# Inverter.net
KiCad netlist of a schematic drawn in EAGLE
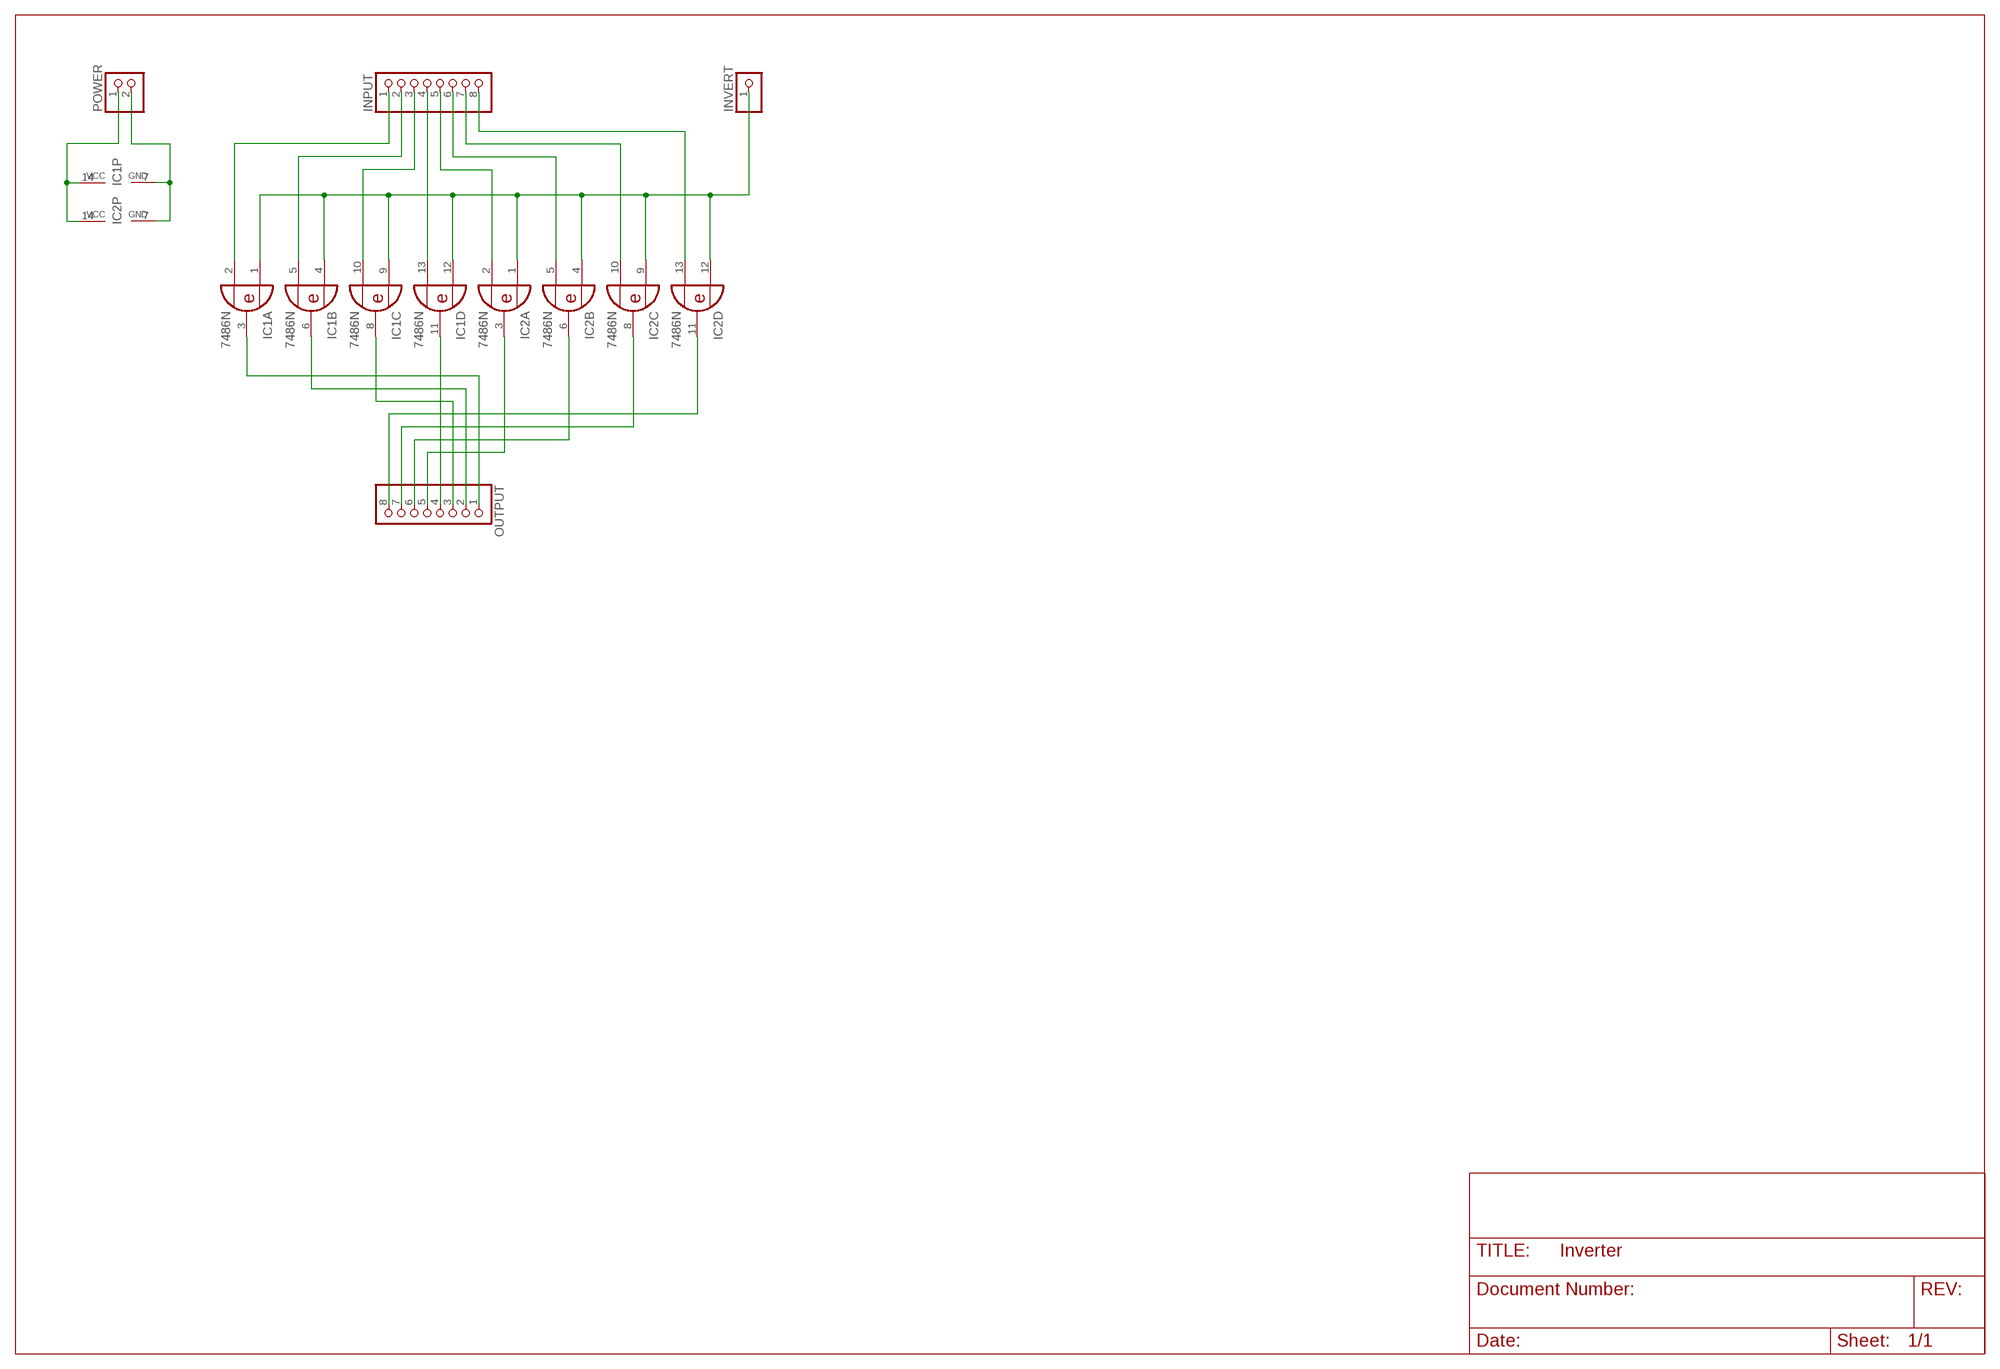
[diagram p0: schematic, sheet 1]

(export (version "E")
  (design (tool "Eeschema 10.0.6"))
  (components
    (comp (ref "IC1")
      (value "7486N")
      (footprint "eagle-import:DIL14")
      (libsource (lib "eagle-import") (part "7486N"))
    )
    (comp (ref "IC2")
      (value "7486N")
      (footprint "eagle-import:DIL14")
      (libsource (lib "eagle-import") (part "7486N"))
    )
    (comp (ref "INPUT")
      (value "PINHD-1X8")
      (footprint "eagle-import:1X08")
      (libsource (lib "eagle-import") (part "PINHD-1X8"))
    )
    (comp (ref "INVERT")
      (value "PINHD-1X1")
      (footprint "eagle-import:1X01")
      (libsource (lib "eagle-import") (part "PINHD-1X1"))
    )
    (comp (ref "OUTPUT")
      (value "PINHD-1X8")
      (footprint "eagle-import:1X08")
      (libsource (lib "eagle-import") (part "PINHD-1X8"))
    )
    (comp (ref "POWER")
      (value "PINHD-1X2")
      (footprint "eagle-import:1X02")
      (libsource (lib "eagle-import") (part "PINHD-1X2"))
    )
  )
  (nets
    (net (code "1") (name "Net-(IC1A-I0)") (class "Default")
      (node (ref "IC1") (pin "1") (pinfunction "I0_1") (pintype "input"))
      (node (ref "IC1") (pin "12") (pinfunction "I0_12") (pintype "input"))
      (node (ref "IC1") (pin "4") (pinfunction "I0_4") (pintype "input"))
      (node (ref "IC1") (pin "9") (pinfunction "I0_9") (pintype "input"))
      (node (ref "IC2") (pin "1") (pinfunction "I0_1") (pintype "input"))
      (node (ref "IC2") (pin "12") (pinfunction "I0_12") (pintype "input"))
      (node (ref "IC2") (pin "4") (pinfunction "I0_4") (pintype "input"))
      (node (ref "IC2") (pin "9") (pinfunction "I0_9") (pintype "input"))
      (node (ref "INVERT") (pin "1") (pinfunction "1_1") (pintype "passive"))
    )
    (net (code "2") (name "Net-(IC1A-I1)") (class "Default")
      (node (ref "IC1") (pin "2") (pinfunction "I1_2") (pintype "input"))
      (node (ref "INPUT") (pin "1") (pinfunction "1_1") (pintype "passive"))
    )
    (net (code "3") (name "Net-(IC1A-O)") (class "Default")
      (node (ref "IC1") (pin "3") (pinfunction "O_3") (pintype "output"))
      (node (ref "OUTPUT") (pin "1") (pinfunction "1_1") (pintype "passive"))
    )
    (net (code "4") (name "Net-(IC1B-I1)") (class "Default")
      (node (ref "IC1") (pin "5") (pinfunction "I1_5") (pintype "input"))
      (node (ref "INPUT") (pin "2") (pinfunction "2_2") (pintype "passive"))
    )
    (net (code "5") (name "Net-(IC1B-O)") (class "Default")
      (node (ref "IC1") (pin "6") (pinfunction "O_6") (pintype "output"))
      (node (ref "OUTPUT") (pin "2") (pinfunction "2_2") (pintype "passive"))
    )
    (net (code "6") (name "Net-(IC1C-I1)") (class "Default")
      (node (ref "IC1") (pin "10") (pinfunction "I1_10") (pintype "input"))
      (node (ref "INPUT") (pin "3") (pinfunction "3_3") (pintype "passive"))
    )
    (net (code "7") (name "Net-(IC1C-O)") (class "Default")
      (node (ref "IC1") (pin "8") (pinfunction "O_8") (pintype "output"))
      (node (ref "OUTPUT") (pin "3") (pinfunction "3_3") (pintype "passive"))
    )
    (net (code "8") (name "Net-(IC1D-I1)") (class "Default")
      (node (ref "IC1") (pin "13") (pinfunction "I1_13") (pintype "input"))
      (node (ref "INPUT") (pin "4") (pinfunction "4_4") (pintype "passive"))
    )
    (net (code "9") (name "Net-(IC1D-O)") (class "Default")
      (node (ref "IC1") (pin "11") (pinfunction "O_11") (pintype "output"))
      (node (ref "OUTPUT") (pin "4") (pinfunction "4_4") (pintype "passive"))
    )
    (net (code "10") (name "Net-(IC1E-GND)") (class "Default")
      (node (ref "IC1") (pin "7") (pinfunction "GND_7") (pintype "power_in"))
      (node (ref "IC2") (pin "7") (pinfunction "GND_7") (pintype "power_in"))
      (node (ref "POWER") (pin "2") (pinfunction "2_2") (pintype "passive"))
    )
    (net (code "11") (name "Net-(IC1E-VCC)") (class "Default")
      (node (ref "IC1") (pin "14") (pinfunction "VCC_14") (pintype "power_in"))
      (node (ref "IC2") (pin "14") (pinfunction "VCC_14") (pintype "power_in"))
      (node (ref "POWER") (pin "1") (pinfunction "1_1") (pintype "passive"))
    )
    (net (code "12") (name "Net-(IC2A-I1)") (class "Default")
      (node (ref "IC2") (pin "2") (pinfunction "I1_2") (pintype "input"))
      (node (ref "INPUT") (pin "5") (pinfunction "5_5") (pintype "passive"))
    )
    (net (code "13") (name "Net-(IC2A-O)") (class "Default")
      (node (ref "IC2") (pin "3") (pinfunction "O_3") (pintype "output"))
      (node (ref "OUTPUT") (pin "5") (pinfunction "5_5") (pintype "passive"))
    )
    (net (code "14") (name "Net-(IC2B-I1)") (class "Default")
      (node (ref "IC2") (pin "5") (pinfunction "I1_5") (pintype "input"))
      (node (ref "INPUT") (pin "6") (pinfunction "6_6") (pintype "passive"))
    )
    (net (code "15") (name "Net-(IC2B-O)") (class "Default")
      (node (ref "IC2") (pin "6") (pinfunction "O_6") (pintype "output"))
      (node (ref "OUTPUT") (pin "6") (pinfunction "6_6") (pintype "passive"))
    )
    (net (code "16") (name "Net-(IC2C-I1)") (class "Default")
      (node (ref "IC2") (pin "10") (pinfunction "I1_10") (pintype "input"))
      (node (ref "INPUT") (pin "7") (pinfunction "7_7") (pintype "passive"))
    )
    (net (code "17") (name "Net-(IC2C-O)") (class "Default")
      (node (ref "IC2") (pin "8") (pinfunction "O_8") (pintype "output"))
      (node (ref "OUTPUT") (pin "7") (pinfunction "7_7") (pintype "passive"))
    )
    (net (code "18") (name "Net-(IC2D-I1)") (class "Default")
      (node (ref "IC2") (pin "13") (pinfunction "I1_13") (pintype "input"))
      (node (ref "INPUT") (pin "8") (pinfunction "8_8") (pintype "passive"))
    )
    (net (code "19") (name "Net-(IC2D-O)") (class "Default")
      (node (ref "IC2") (pin "11") (pinfunction "O_11") (pintype "output"))
      (node (ref "OUTPUT") (pin "8") (pinfunction "8_8") (pintype "passive"))
    )
  )
)
